# ttl_net.net
KiCad netlist of a schematic drawn in EAGLE
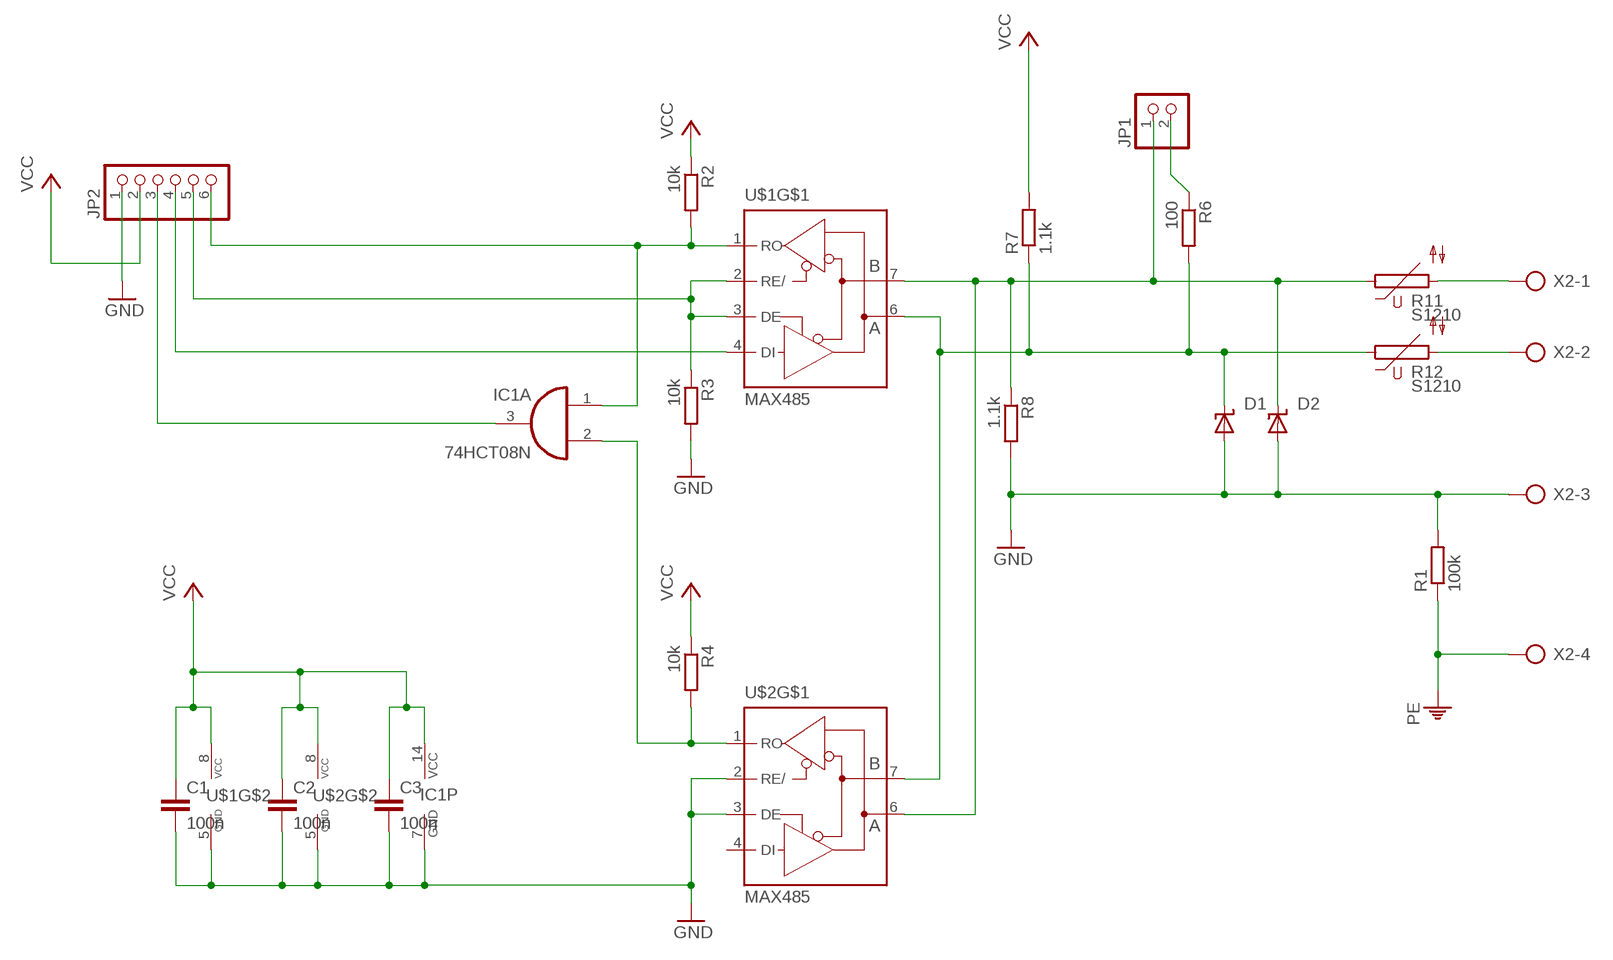
[diagram p0: schematic, sheet 1]

(export (version "E")
  (design (tool "Eeschema 10.0.6"))
  (components
    (comp (ref "C1")
      (value "100n")
      (footprint "eagle-import:C050-035X075")
      (libsource (lib "eagle-import") (part "C-EU050-035X075"))
    )
    (comp (ref "C2")
      (value "100n")
      (footprint "eagle-import:C050-035X075")
      (libsource (lib "eagle-import") (part "C-EU050-035X075"))
    )
    (comp (ref "C3")
      (value "100n")
      (footprint "eagle-import:C050-035X075")
      (libsource (lib "eagle-import") (part "C-EU050-035X075"))
    )
    (comp (ref "D1")
      (value "SUPPRESSOR-SMBJ")
      (footprint "eagle-import:SMBJ")
      (libsource (lib "eagle-import") (part "SUPPRESSOR-SMBJ"))
    )
    (comp (ref "D2")
      (value "SUPPRESSOR-SMBJ")
      (footprint "eagle-import:SMBJ")
      (libsource (lib "eagle-import") (part "SUPPRESSOR-SMBJ"))
    )
    (comp (ref "IC1")
      (value "74HCT08N")
      (footprint "eagle-import:DIL14")
      (libsource (lib "eagle-import") (part "7408NHCT"))
    )
    (comp (ref "JP1")
      (value "PINHD-1X2")
      (footprint "eagle-import:1X02")
      (libsource (lib "eagle-import") (part "PINHD-1X2"))
    )
    (comp (ref "JP2")
      (value "PINHD-1X6")
      (footprint "eagle-import:1X06")
      (libsource (lib "eagle-import") (part "PINHD-1X6"))
    )
    (comp (ref "R1")
      (value "100k")
      (footprint "eagle-import:0204_7")
      (libsource (lib "eagle-import") (part "R-EU_0204/7"))
    )
    (comp (ref "R2")
      (value "10k")
      (footprint "eagle-import:0204_7")
      (libsource (lib "eagle-import") (part "R-EU_0204/7"))
    )
    (comp (ref "R3")
      (value "10k")
      (footprint "eagle-import:0204_7")
      (libsource (lib "eagle-import") (part "R-EU_0204/7"))
    )
    (comp (ref "R4")
      (value "10k")
      (footprint "eagle-import:0204_7")
      (libsource (lib "eagle-import") (part "R-EU_0204/7"))
    )
    (comp (ref "R6")
      (value "100")
      (footprint "eagle-import:0204_7")
      (libsource (lib "eagle-import") (part "R-EU_0204/7"))
    )
    (comp (ref "R7")
      (value "1.1k")
      (footprint "eagle-import:0204_7")
      (libsource (lib "eagle-import") (part "R-EU_0204/7"))
    )
    (comp (ref "R8")
      (value "1.1k")
      (footprint "eagle-import:0204_7")
      (libsource (lib "eagle-import") (part "R-EU_0204/7"))
    )
    (comp (ref "R11")
      (value "S1210")
      (footprint "eagle-import:S1210")
      (libsource (lib "eagle-import") (part "S1210"))
    )
    (comp (ref "R12")
      (value "S1210")
      (footprint "eagle-import:S1210")
      (libsource (lib "eagle-import") (part "S1210"))
    )
    (comp (ref "U$1")
      (value "MAX485")
      (footprint "eagle-import:DIL08")
      (libsource (lib "eagle-import") (part "MAX485"))
    )
    (comp (ref "U$2")
      (value "MAX485")
      (footprint "eagle-import:DIL08")
      (libsource (lib "eagle-import") (part "MAX485"))
    )
    (comp (ref "X2")
      (value "AK500/4")
      (footprint "eagle-import:AK500_4")
      (libsource (lib "eagle-import") (part "AK500/4"))
    )
  )
  (nets
    (net (code "1") (name "GND") (class "Default")
      (node (ref "C1") (pin "2") (pinfunction "2_2") (pintype "passive"))
      (node (ref "C2") (pin "2") (pinfunction "2_2") (pintype "passive"))
      (node (ref "C3") (pin "2") (pinfunction "2_2") (pintype "passive"))
      (node (ref "D1") (pin "A") (pinfunction "A_A") (pintype "passive"))
      (node (ref "D2") (pin "A") (pinfunction "A_A") (pintype "passive"))
      (node (ref "IC1") (pin "7") (pinfunction "GND_7") (pintype "power_in"))
      (node (ref "JP2") (pin "1") (pinfunction "1_1") (pintype "passive"))
      (node (ref "R1") (pin "2") (pinfunction "2_2") (pintype "passive"))
      (node (ref "R3") (pin "2") (pinfunction "2_2") (pintype "passive"))
      (node (ref "R8") (pin "2") (pinfunction "2_2") (pintype "passive"))
      (node (ref "U$1") (pin "5") (pinfunction "GND_5") (pintype "power_in"))
      (node (ref "U$2") (pin "2") (pinfunction "RE/_2") (pintype "input"))
      (node (ref "U$2") (pin "3") (pinfunction "DE_3") (pintype "input"))
      (node (ref "U$2") (pin "5") (pinfunction "GND_5") (pintype "power_in"))
      (node (ref "X2") (pin "3") (pinfunction "KL_3") (pintype "passive"))
    )
    (net (code "2") (name "Net-(IC1A-I0)") (class "Default")
      (node (ref "IC1") (pin "1") (pinfunction "I0_1") (pintype "input"))
      (node (ref "JP2") (pin "6") (pinfunction "6_6") (pintype "passive"))
      (node (ref "R2") (pin "2") (pinfunction "2_2") (pintype "passive"))
      (node (ref "U$1") (pin "1") (pinfunction "RO_1") (pintype "output"))
    )
    (net (code "3") (name "Net-(IC1A-I1)") (class "Default")
      (node (ref "IC1") (pin "2") (pinfunction "I1_2") (pintype "input"))
      (node (ref "R4") (pin "2") (pinfunction "2_2") (pintype "passive"))
      (node (ref "U$2") (pin "1") (pinfunction "RO_1") (pintype "output"))
    )
    (net (code "4") (name "Net-(IC1A-O)") (class "Default")
      (node (ref "IC1") (pin "3") (pinfunction "O_3") (pintype "output"))
      (node (ref "JP2") (pin "3") (pinfunction "3_3") (pintype "passive"))
    )
    (net (code "5") (name "Net-(JP1-Pad2)") (class "Default")
      (node (ref "JP1") (pin "2") (pinfunction "2_2") (pintype "passive"))
      (node (ref "R6") (pin "1") (pinfunction "1_1") (pintype "passive"))
    )
    (net (code "6") (name "Net-(U$1A-A)") (class "Default")
      (node (ref "D1") (pin "C") (pinfunction "C_C") (pintype "passive"))
      (node (ref "R12") (pin "1") (pinfunction "1_1") (pintype "passive"))
      (node (ref "R6") (pin "2") (pinfunction "2_2") (pintype "passive"))
      (node (ref "R7") (pin "1") (pinfunction "1_1") (pintype "passive"))
      (node (ref "U$1") (pin "6") (pinfunction "A_6") (pintype "passive"))
      (node (ref "U$2") (pin "7") (pinfunction "B_7") (pintype "passive"))
    )
    (net (code "7") (name "Net-(U$1A-B)") (class "Default")
      (node (ref "D2") (pin "C") (pinfunction "C_C") (pintype "passive"))
      (node (ref "JP1") (pin "1") (pinfunction "1_1") (pintype "passive"))
      (node (ref "R11") (pin "1") (pinfunction "1_1") (pintype "passive"))
      (node (ref "R8") (pin "1") (pinfunction "1_1") (pintype "passive"))
      (node (ref "U$1") (pin "7") (pinfunction "B_7") (pintype "passive"))
      (node (ref "U$2") (pin "6") (pinfunction "A_6") (pintype "passive"))
    )
    (net (code "8") (name "Net-(U$1A-DE)") (class "Default")
      (node (ref "JP2") (pin "5") (pinfunction "5_5") (pintype "passive"))
      (node (ref "R3") (pin "1") (pinfunction "1_1") (pintype "passive"))
      (node (ref "U$1") (pin "2") (pinfunction "RE/_2") (pintype "input"))
      (node (ref "U$1") (pin "3") (pinfunction "DE_3") (pintype "input"))
    )
    (net (code "9") (name "Net-(U$1A-DI)") (class "Default")
      (node (ref "JP2") (pin "4") (pinfunction "4_4") (pintype "passive"))
      (node (ref "U$1") (pin "4") (pinfunction "DI_4") (pintype "input"))
    )
    (net (code "10") (name "Net-(X2A-KL)") (class "Default")
      (node (ref "R11") (pin "2") (pinfunction "2_2") (pintype "passive"))
      (node (ref "X2") (pin "1") (pinfunction "KL_1") (pintype "passive"))
    )
    (net (code "11") (name "Net-(X2B-KL)") (class "Default")
      (node (ref "R12") (pin "2") (pinfunction "2_2") (pintype "passive"))
      (node (ref "X2") (pin "2") (pinfunction "KL_2") (pintype "passive"))
    )
    (net (code "12") (name "PE") (class "Default")
      (node (ref "R1") (pin "1") (pinfunction "1_1") (pintype "passive"))
      (node (ref "X2") (pin "4") (pinfunction "KL_4") (pintype "passive"))
    )
    (net (code "13") (name "VCC") (class "Default")
      (node (ref "C1") (pin "1") (pinfunction "1_1") (pintype "passive"))
      (node (ref "C2") (pin "1") (pinfunction "1_1") (pintype "passive"))
      (node (ref "C3") (pin "1") (pinfunction "1_1") (pintype "passive"))
      (node (ref "IC1") (pin "14") (pinfunction "VCC_14") (pintype "power_in"))
      (node (ref "JP2") (pin "2") (pinfunction "2_2") (pintype "passive"))
      (node (ref "R2") (pin "1") (pinfunction "1_1") (pintype "passive"))
      (node (ref "R4") (pin "1") (pinfunction "1_1") (pintype "passive"))
      (node (ref "R7") (pin "2") (pinfunction "2_2") (pintype "passive"))
      (node (ref "U$1") (pin "8") (pinfunction "VCC_8") (pintype "power_in"))
      (node (ref "U$2") (pin "8") (pinfunction "VCC_8") (pintype "power_in"))
    )
    (net (code "14") (name "unconnected-(U$2A-DI-Pad4)") (class "Default")
      (node (ref "U$2") (pin "4") (pinfunction "DI_4") (pintype "input"))
    )
  )
)
